# board_side.net
KiCad netlist of a schematic drawn in Altium Designer
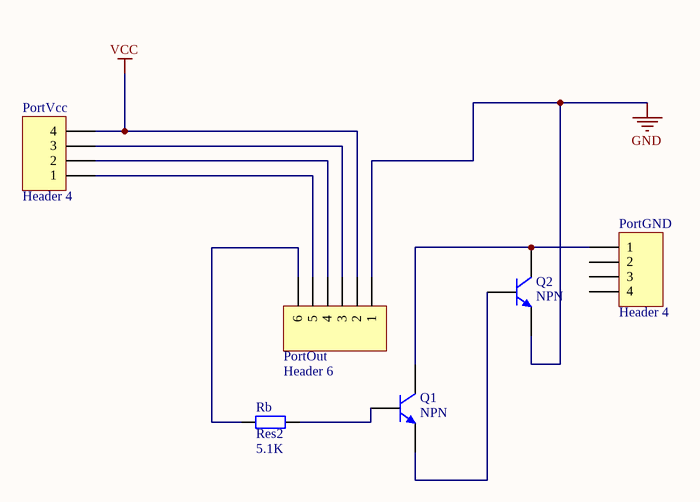
[diagram p0: board_side.SchDoc]

(export (version "E")
  (design (tool "Eeschema 10.0.6"))
  (components
    (comp (ref "PortGND")
      (value "Header 4")
      (footprint "HDR1X4")
      (description "Header, 4-Pin")
      (fields (field (name "PUBLISHER") "Altium Limited"))
      (libsource (lib "Miscellaneous Connectors") (part "Header 4"))
    )
    (comp (ref "PortOut")
      (value "Header 6")
      (footprint "HDR1X6")
      (description "Header, 6-Pin")
      (fields (field (name "PUBLISHER") "Altium Limited"))
      (libsource (lib "Miscellaneous Connectors") (part "Header 6"))
    )
    (comp (ref "PortVcc")
      (value "Header 4")
      (footprint "HDR1X4")
      (description "Header, 4-Pin")
      (fields (field (name "PUBLISHER") "Altium Limited"))
      (libsource (lib "") (part "Header 4_1"))
    )
    (comp (ref "Q1")
      (value "NPN")
      (footprint "TO-226-AA")
      (description "NPN Bipolar Transistor")
      (fields (field (name "PUBLISHER") "Altium Limited"))
      (libsource (lib "Miscellaneous Devices") (part "NPN"))
    )
    (comp (ref "Q2")
      (value "NPN")
      (footprint "TO-226-AA")
      (description "NPN Bipolar Transistor")
      (fields (field (name "PUBLISHER") "Altium Limited"))
      (libsource (lib "Miscellaneous Devices") (part "NPN"))
    )
    (comp (ref "Rb")
      (value "Res2")
      (footprint "AXIAL-0.4")
      (description "Resistor")
      (fields (field (name "ALTIUM_VALUE") "5.1K") (field (name "PUBLISHER") "Altium Limited"))
      (libsource (lib "Miscellaneous Devices") (part "Res2"))
    )
  )
  (nets
    (net (code "1") (name "GND") (class "Default")
      (node (ref "PortOut") (pin "1") (pinfunction "1_1") (pintype "passive"))
      (node (ref "Q2") (pin "3") (pinfunction "E_3") (pintype "passive"))
    )
    (net (code "2") (name "Net-(PortOut-Pad3)") (class "Default")
      (node (ref "PortOut") (pin "3") (pinfunction "3_3") (pintype "passive"))
      (node (ref "PortVcc") (pin "3") (pinfunction "3_3") (pintype "passive"))
    )
    (net (code "3") (name "Net-(PortOut-Pad4)") (class "Default")
      (node (ref "PortOut") (pin "4") (pinfunction "4_4") (pintype "passive"))
      (node (ref "PortVcc") (pin "2") (pinfunction "2_2") (pintype "passive"))
    )
    (net (code "4") (name "Net-(PortOut-Pad5)") (class "Default")
      (node (ref "PortOut") (pin "5") (pinfunction "5_5") (pintype "passive"))
      (node (ref "PortVcc") (pin "1") (pinfunction "1_1") (pintype "passive"))
    )
    (net (code "5") (name "Net-(PortOut-Pad6)") (class "Default")
      (node (ref "PortOut") (pin "6") (pinfunction "6_6") (pintype "passive"))
      (node (ref "Rb") (pin "1") (pinfunction "1_1") (pintype "passive"))
    )
    (net (code "6") (name "Net-(Q1-B)") (class "Default")
      (node (ref "Q1") (pin "2") (pinfunction "B_2") (pintype "passive"))
      (node (ref "Rb") (pin "2") (pinfunction "2_2") (pintype "passive"))
    )
    (net (code "7") (name "Net-(Q1-C)") (class "Default")
      (node (ref "PortGND") (pin "1") (pinfunction "1_1") (pintype "passive"))
      (node (ref "Q1") (pin "1") (pinfunction "C_1") (pintype "passive"))
      (node (ref "Q2") (pin "1") (pinfunction "C_1") (pintype "passive"))
    )
    (net (code "8") (name "Net-(Q1-E)") (class "Default")
      (node (ref "Q1") (pin "3") (pinfunction "E_3") (pintype "passive"))
      (node (ref "Q2") (pin "2") (pinfunction "B_2") (pintype "passive"))
    )
    (net (code "9") (name "VCC") (class "Default")
      (node (ref "PortOut") (pin "2") (pinfunction "2_2") (pintype "passive"))
      (node (ref "PortVcc") (pin "4") (pinfunction "4_4") (pintype "passive"))
    )
    (net (code "10") (name "unconnected-(PortGND-Pad2)") (class "Default")
      (node (ref "PortGND") (pin "2") (pinfunction "2_2") (pintype "passive"))
    )
    (net (code "11") (name "unconnected-(PortGND-Pad3)") (class "Default")
      (node (ref "PortGND") (pin "3") (pinfunction "3_3") (pintype "passive"))
    )
    (net (code "12") (name "unconnected-(PortGND-Pad4)") (class "Default")
      (node (ref "PortGND") (pin "4") (pinfunction "4_4") (pintype "passive"))
    )
  )
)
